# PDM-S04-V00-Microcontroller.net
KiCad netlist of a schematic drawn in Altium Designer
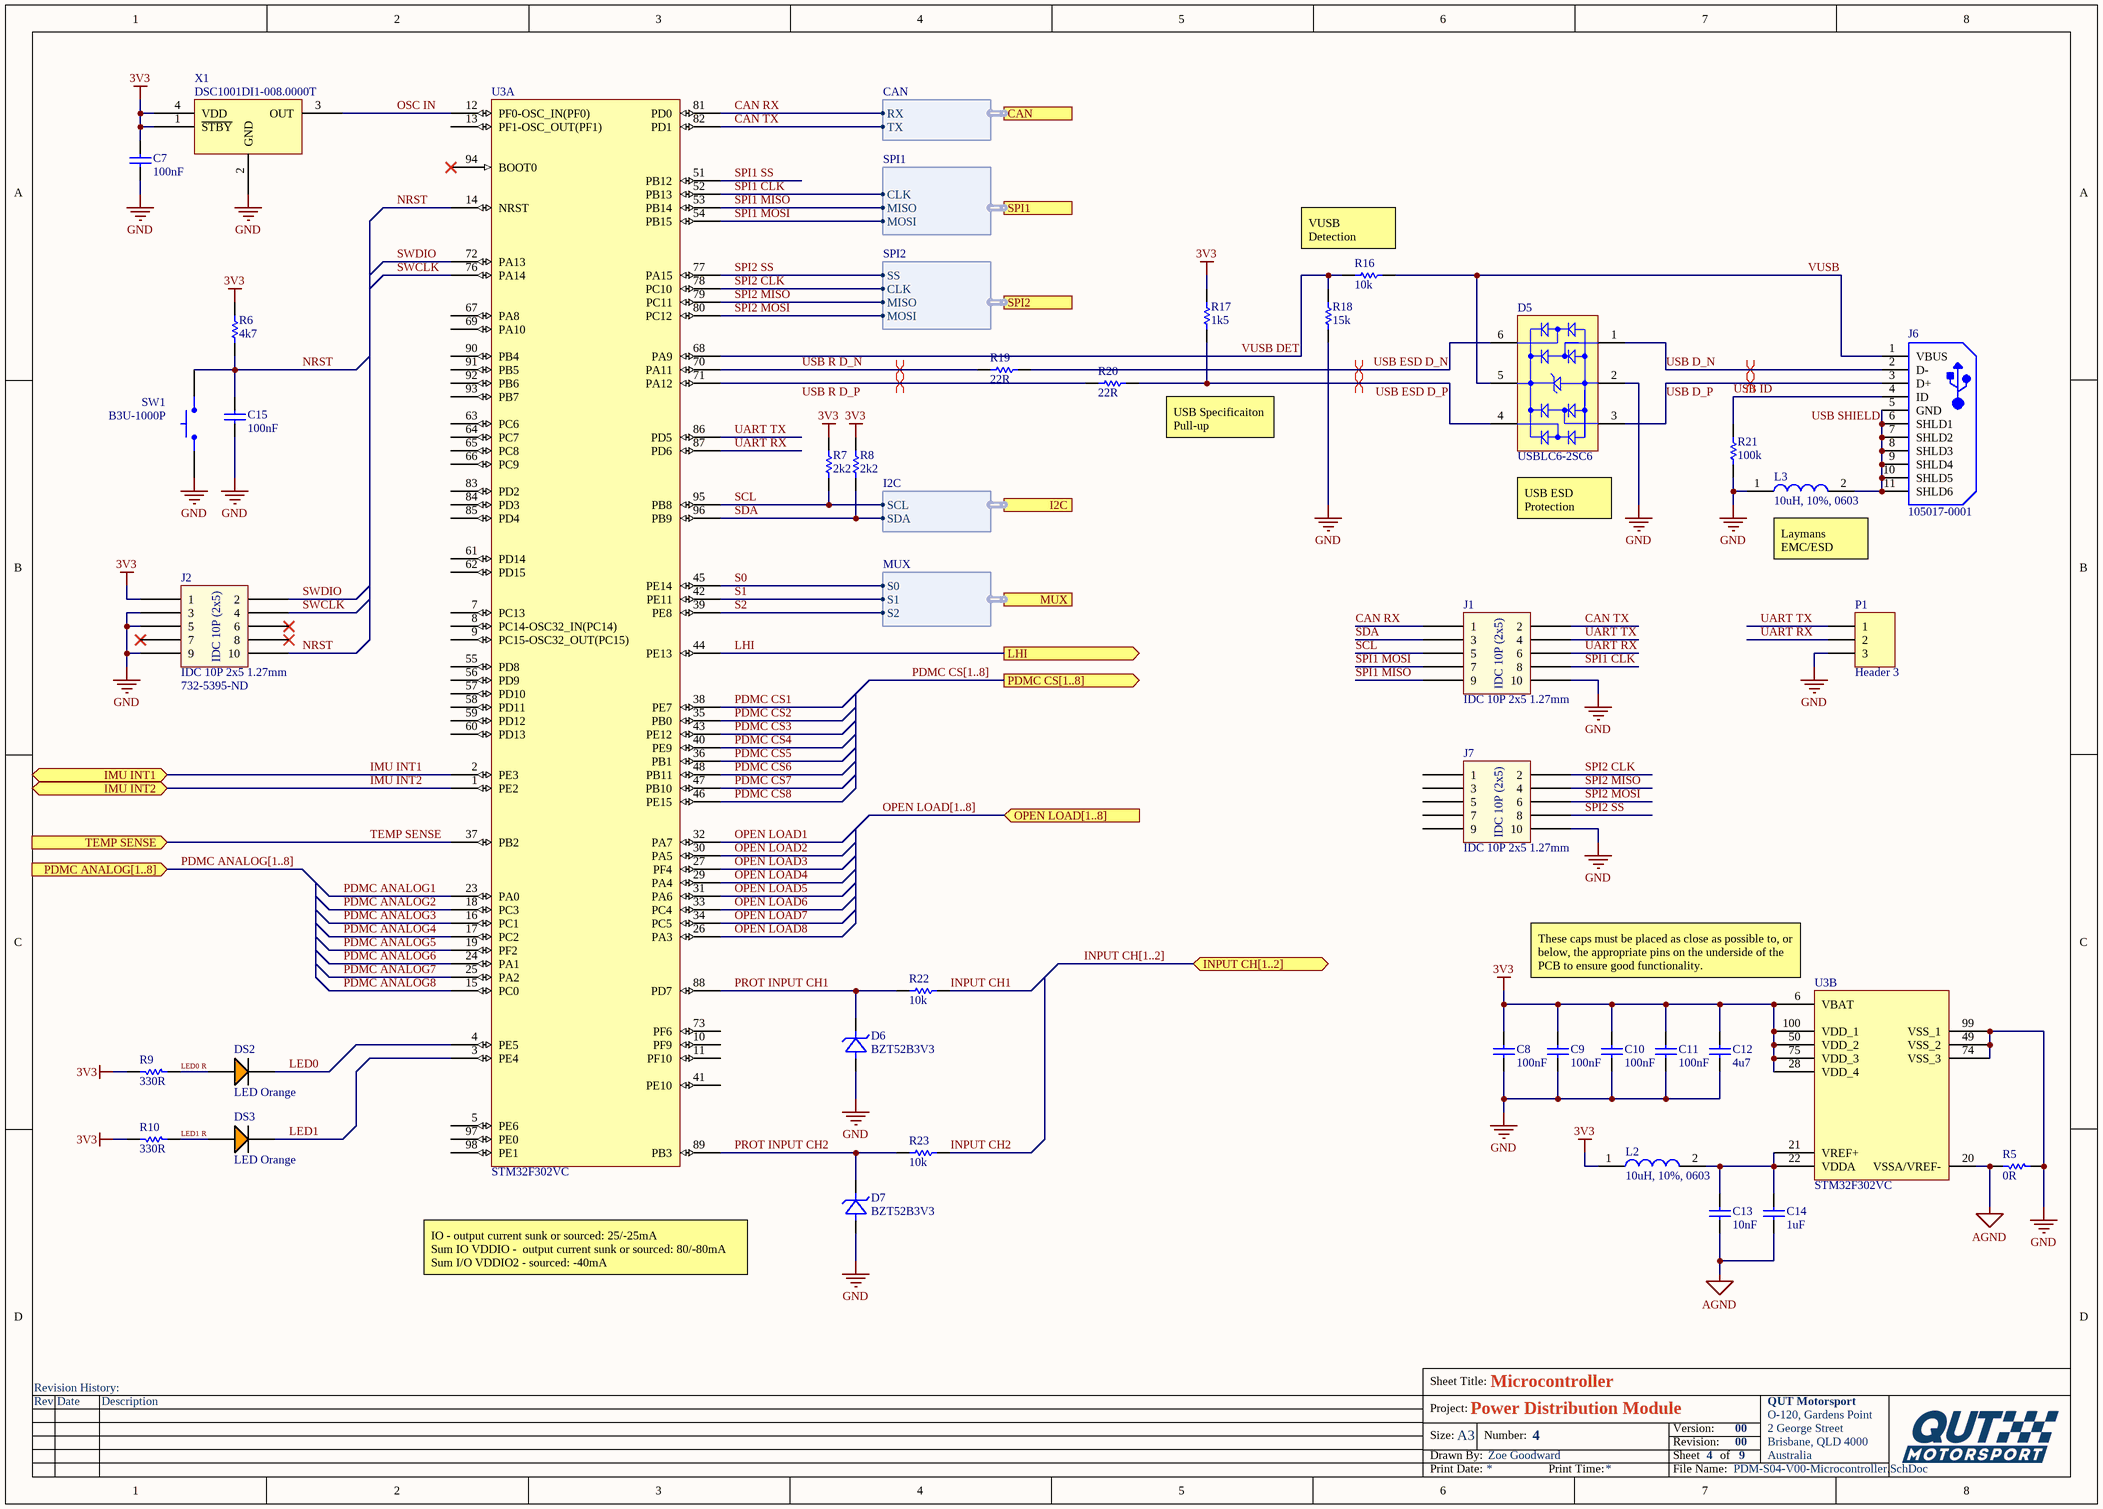
[diagram p0: PDM-S04-V00-Microcontroller.SchDoc]

(export (version "E")
  (design (tool "Eeschema 10.0.6"))
  (components
    (comp (ref "C7")
      (value "100nF")
      (footprint "Cap_Ceramic_0603")
      (description "Capacitor, Ceramic, SMD, 100nF, 50V, 5%, X7R, 0603")
      (libsource (lib "StandardCapacitors") (part "100nF 50V 5% X7R 0603"))
    )
    (comp (ref "C8")
      (value "100nF")
      (footprint "Cap_Ceramic_0603")
      (description "Capacitor, Ceramic, SMD, 100nF, 50V, 5%, X7R, 0603")
      (libsource (lib "StandardCapacitors") (part "100nF 50V 5% X7R 0603"))
    )
    (comp (ref "C9")
      (value "100nF")
      (footprint "Cap_Ceramic_0603")
      (description "Capacitor, Ceramic, SMD, 100nF, 50V, 5%, X7R, 0603")
      (libsource (lib "StandardCapacitors") (part "100nF 50V 5% X7R 0603"))
    )
    (comp (ref "C10")
      (value "100nF")
      (footprint "Cap_Ceramic_0603")
      (description "Capacitor, Ceramic, SMD, 100nF, 50V, 5%, X7R, 0603")
      (libsource (lib "StandardCapacitors") (part "100nF 50V 5% X7R 0603"))
    )
    (comp (ref "C11")
      (value "100nF")
      (footprint "Cap_Ceramic_0603")
      (description "Capacitor, Ceramic, SMD, 100nF, 50V, 5%, X7R, 0603")
      (libsource (lib "StandardCapacitors") (part "100nF 50V 5% X7R 0603"))
    )
    (comp (ref "C12")
      (value "4u7")
      (footprint "Cap_Ceramic_0603")
      (description "Capacitor, Ceramic, SMD, 4u7, 50V, 5%, X7R, 0603")
      (libsource (lib "StandardCapacitors") (part "4u7 50V 5% X7R 0603"))
    )
    (comp (ref "C13")
      (value "10nF")
      (footprint "Cap_Ceramic_0603")
      (description "Capacitor, Ceramic, SMD, 10nF, 50V, 5%, X7R, 0603")
      (libsource (lib "StandardCapacitors") (part "10nF 50V 5% X7R 0603"))
    )
    (comp (ref "C14")
      (value "1uF")
      (footprint "Cap_Ceramic_0603")
      (description "Capacitor, Ceramic, SMD, 1uF, 25V, 5%, X7R, 0603")
      (libsource (lib "StandardCapacitors") (part "1uF 25V 5% X7R 0603"))
    )
    (comp (ref "C15")
      (value "100nF")
      (footprint "Cap_Ceramic_0603")
      (description "Capacitor, Ceramic, SMD, 100nF, 50V, 5%, X7R, 0603")
      (libsource (lib "StandardCapacitors") (part "100nF 50V 5% X7R 0603"))
    )
    (comp (ref "D5")
      (value "USBLC6-2SC6")
      (footprint "STM-SOT23-6L_V")
      (description "Very low capacitance ESD protection, 3.5 pF, -40 to 125 degC, 6-Pin SOT23, RoHS, Tape and Reel")
      (fields (field (name "MANUFACTURER") "STMicroelectronics"))
      (libsource (lib "Altium Content Vault") (part "STM-USB_DVI_HDMIULC6-4SC6X-SOT23-6L"))
    )
    (comp (ref "D6")
      (value "BZT52B3V3")
      (footprint "SOD123")
      (description "Diode, SMD, Zener, 3.3V, 2%, 410mW, SOD-123")
      (libsource (lib "QUTMS_DiodeLibrary") (part "BZT52B3V3"))
    )
    (comp (ref "D7")
      (value "BZT52B3V3")
      (footprint "SOD123")
      (description "Diode, SMD, Zener, 3.3V, 2%, 410mW, SOD-123")
      (libsource (lib "QUTMS_DiodeLibrary") (part "BZT52B3V3"))
    )
    (comp (ref "DS2")
      (value "LED Orange")
      (footprint "LED ORANGE 0603")
      (libsource (lib "QUTMS_LEDLibrary") (part "LED ORANGE 0603"))
    )
    (comp (ref "DS3")
      (value "LED Orange")
      (footprint "LED ORANGE 0603")
      (libsource (lib "QUTMS_LEDLibrary") (part "LED ORANGE 0603"))
    )
    (comp (ref "J1")
      (value "IDC 10P 2x5 1.27mm")
      (footprint "IDC 1.27MM 10P")
      (libsource (lib "IDCConnectors") (part "IDC 10P 2x5 1.27mm"))
    )
    (comp (ref "J2")
      (value "IDC 10P 2x5 1.27mm")
      (footprint "IDC 1.27MM 10P")
      (libsource (lib "IDCConnectors") (part "IDC 10P 2x5 1.27mm"))
    )
    (comp (ref "J6")
      (value "105017-0001")
      (footprint "USB-MICRO-B_V")
      (fields (field (name "MANUFACTURER") "Molex"))
      (libsource (lib "Altium Content Vault") (part "USB-5-6SHLD"))
    )
    (comp (ref "J7")
      (value "IDC 10P 2x5 1.27mm")
      (footprint "IDC 1.27MM 10P")
      (libsource (lib "IDCConnectors") (part "IDC 10P 2x5 1.27mm"))
    )
    (comp (ref "L2")
      (value "10uH, 10%, 0603")
      (footprint "Inductor_0603")
      (libsource (lib "QUTMS_InductorLibrary") (part "10uH, 10%, 0603"))
    )
    (comp (ref "L3")
      (value "10uH, 10%, 0603")
      (footprint "Inductor_0603")
      (libsource (lib "QUTMS_InductorLibrary") (part "10uH, 10%, 0603"))
    )
    (comp (ref "P1")
      (value "Header 3")
      (footprint "HDR1X3")
      (description "Header, 3-Pin")
      (fields (field (name "PUBLISHER") "Altium Limited"))
      (libsource (lib "Miscellaneous Connectors") (part "Header 3"))
    )
    (comp (ref "R5")
      (value "0R")
      (footprint "Res_ThinFilm_0603")
      (description "Resistor, SMD, 0R, 0.1W, 5%, 0603")
      (libsource (lib "StandardResistors") (part "0R 5% 0603"))
    )
    (comp (ref "R6")
      (value "4k7")
      (footprint "Res_ThinFilm_0603")
      (description "Resistor, SMD, 4k7, 0.1W, 5%, 0603")
      (libsource (lib "StandardResistors") (part "4k7 5% 0603"))
    )
    (comp (ref "R7")
      (value "2k2")
      (footprint "Res_ThinFilm_0603")
      (description "Resistor, SMD, 2k2, 0.1W, 5%, 0603")
      (libsource (lib "StandardResistors") (part "2k2 5% 0603"))
    )
    (comp (ref "R8")
      (value "2k2")
      (footprint "Res_ThinFilm_0603")
      (description "Resistor, SMD, 2k2, 0.1W, 5%, 0603")
      (libsource (lib "StandardResistors") (part "2k2 5% 0603"))
    )
    (comp (ref "R9")
      (value "330R")
      (footprint "Res_ThinFilm_0603")
      (description "Resistor, SMD, 330R, 0.1W, 5%, 0603")
      (libsource (lib "StandardResistors") (part "330R 5% 0603"))
    )
    (comp (ref "R10")
      (value "330R")
      (footprint "Res_ThinFilm_0603")
      (description "Resistor, SMD, 330R, 0.1W, 5%, 0603")
      (libsource (lib "StandardResistors") (part "330R 5% 0603"))
    )
    (comp (ref "R16")
      (value "10k")
      (footprint "Res_ThinFilm_0603")
      (description "Resistor, SMD, 10k, 0.1W, 1%, 0603")
      (libsource (lib "StandardResistors") (part "10k 1% 0603"))
    )
    (comp (ref "R17")
      (value "1k5")
      (footprint "Res_ThinFilm_0603")
      (description "Resistor, SMD, 1k5, 0.1W, 5%, 0603")
      (libsource (lib "StandardResistors") (part "1k5 5% 0603"))
    )
    (comp (ref "R18")
      (value "15k")
      (footprint "Res_ThinFilm_0603")
      (description "Resistor, SMD, 15k, 0.1W, 5%, 0603")
      (libsource (lib "StandardResistors") (part "15k 5% 0603"))
    )
    (comp (ref "R19")
      (value "22R")
      (footprint "Res_ThinFilm_0603")
      (description "Resistor, SMD, 22R, 0.1W, 5%, 0603")
      (libsource (lib "StandardResistors") (part "22R 5% 0603"))
    )
    (comp (ref "R20")
      (value "22R")
      (footprint "Res_ThinFilm_0603")
      (description "Resistor, SMD, 22R, 0.1W, 5%, 0603")
      (libsource (lib "StandardResistors") (part "22R 5% 0603"))
    )
    (comp (ref "R21")
      (value "100k")
      (footprint "Res_ThinFilm_0603")
      (description "Resistor, SMD, 100k, 0.1W, 5%, 0603")
      (libsource (lib "StandardResistors") (part "100k 5%, 0603"))
    )
    (comp (ref "R22")
      (value "10k")
      (footprint "Res_ThinFilm_0603")
      (description "Resistor, SMD, 10k, 0.1W, 5%, 0603")
      (libsource (lib "StandardResistors") (part "10k 5% 0603"))
    )
    (comp (ref "R23")
      (value "10k")
      (footprint "Res_ThinFilm_0603")
      (description "Resistor, SMD, 10k, 0.1W, 5%, 0603")
      (libsource (lib "StandardResistors") (part "10k 5% 0603"))
    )
    (comp (ref "SW1")
      (value "B3U-1000P")
      (footprint "BTN B3U-1000P")
      (description "Omron B3U-1000P Ultra Miniture Switch")
      (libsource (lib "QUTMS_SwitchLibrary") (part "BTN B3U-1000P"))
    )
    (comp (ref "U3")
      (value "STM32F302VC")
      (footprint "STM-LQFP100")
      (description "ARM Cortex-M4 32-bit MCU, 256 KB Flash, 32 KB Internal RAM, 87 I/Os, 100-pin LQFP, -40 to 85 degC")
      (fields (field (name "PARTNUMBER") "STM32F302VCT6"))
      (libsource (lib "QUTMS_STM32Library") (part "STM32F302VC"))
    )
    (comp (ref "X1")
      (value "DSC1001DI1-008.0000T")
      (footprint "DSC1001DI1-008.0000TCT-ND")
      (description "8MHz XO (Standard) CMOS Oscillator 1.8 ~ 3.3V Standby (Power Down) 4-SMD, No Lead")
      (libsource (lib "QUTMS_CrystalLibrary") (part "DSC1001DI1-008.0000T"))
    )
  )
  (nets
    (net (code "6") (name "/CAN RX") (class "Default")
      (node (ref "J1") (pin "1") (pinfunction "1_1") (pintype "passive"))
      (node (ref "U3") (pin "81") (pinfunction "PD0_81") (pintype "bidirectional"))
    )
    (net (code "7") (name "/CAN TX") (class "Default")
      (node (ref "J1") (pin "2") (pinfunction "2_2") (pintype "passive"))
      (node (ref "U3") (pin "82") (pinfunction "PD1_82") (pintype "bidirectional"))
    )
    (net (code "8") (name "/IMU INT1") (class "Default")
      (node (ref "U3") (pin "2") (pinfunction "PE3_2") (pintype "bidirectional"))
    )
    (net (code "9") (name "/IMU INT2") (class "Default")
      (node (ref "U3") (pin "1") (pinfunction "PE2_1") (pintype "bidirectional"))
    )
    (net (code "10") (name "/INPUT CH1") (class "Default")
      (node (ref "R22") (pin "2") (pinfunction "2_2") (pintype "passive"))
    )
    (net (code "11") (name "/INPUT CH2") (class "Default")
      (node (ref "R23") (pin "2") (pinfunction "2_2") (pintype "passive"))
    )
    (net (code "12") (name "/LED0") (class "Default")
      (node (ref "DS2") (pin "2") (pinfunction "C_2") (pintype "passive"))
      (node (ref "U3") (pin "4") (pinfunction "PE5_4") (pintype "bidirectional"))
    )
    (net (code "13") (name "/LED0 R") (class "Default")
      (node (ref "DS2") (pin "1") (pinfunction "A_1") (pintype "passive"))
      (node (ref "R9") (pin "1") (pinfunction "1_1") (pintype "passive"))
    )
    (net (code "14") (name "/LED1") (class "Default")
      (node (ref "DS3") (pin "2") (pinfunction "C_2") (pintype "passive"))
      (node (ref "U3") (pin "3") (pinfunction "PE4_3") (pintype "bidirectional"))
    )
    (net (code "15") (name "/LED1 R") (class "Default")
      (node (ref "DS3") (pin "1") (pinfunction "A_1") (pintype "passive"))
      (node (ref "R10") (pin "1") (pinfunction "1_1") (pintype "passive"))
    )
    (net (code "16") (name "/LHI") (class "Default")
      (node (ref "U3") (pin "44") (pinfunction "PE13_44") (pintype "bidirectional"))
    )
    (net (code "17") (name "/NRST") (class "Default")
      (node (ref "C15") (pin "2") (pinfunction "2_2") (pintype "passive"))
      (node (ref "J2") (pin "10") (pinfunction "10_10") (pintype "passive"))
      (node (ref "R6") (pin "1") (pinfunction "1_1") (pintype "passive"))
      (node (ref "SW1") (pin "2") (pinfunction "2_2") (pintype "passive"))
      (node (ref "U3") (pin "14") (pinfunction "NRST_14") (pintype "bidirectional"))
    )
    (net (code "18") (name "/OPEN LOAD1") (class "Default")
      (node (ref "U3") (pin "32") (pinfunction "PA7_32") (pintype "bidirectional"))
    )
    (net (code "19") (name "/OPEN LOAD2") (class "Default")
      (node (ref "U3") (pin "30") (pinfunction "PA5_30") (pintype "bidirectional"))
    )
    (net (code "20") (name "/OPEN LOAD3") (class "Default")
      (node (ref "U3") (pin "27") (pinfunction "PF4_27") (pintype "bidirectional"))
    )
    (net (code "21") (name "/OPEN LOAD4") (class "Default")
      (node (ref "U3") (pin "29") (pinfunction "PA4_29") (pintype "bidirectional"))
    )
    (net (code "22") (name "/OPEN LOAD5") (class "Default")
      (node (ref "U3") (pin "31") (pinfunction "PA6_31") (pintype "bidirectional"))
    )
    (net (code "23") (name "/OPEN LOAD6") (class "Default")
      (node (ref "U3") (pin "33") (pinfunction "PC4_33") (pintype "bidirectional"))
    )
    (net (code "24") (name "/OPEN LOAD7") (class "Default")
      (node (ref "U3") (pin "34") (pinfunction "PC5_34") (pintype "bidirectional"))
    )
    (net (code "25") (name "/OPEN LOAD8") (class "Default")
      (node (ref "U3") (pin "26") (pinfunction "PA3_26") (pintype "bidirectional"))
    )
    (net (code "26") (name "/OSC IN") (class "Default")
      (node (ref "U3") (pin "12") (pinfunction "PF0-OSC_IN(PF0)_12") (pintype "bidirectional"))
      (node (ref "X1") (pin "3") (pinfunction "OUT_3") (pintype "passive"))
    )
    (net (code "27") (name "/PDMC ANALOG1") (class "Default")
      (node (ref "U3") (pin "23") (pinfunction "PA0_23") (pintype "bidirectional"))
    )
    (net (code "28") (name "/PDMC ANALOG2") (class "Default")
      (node (ref "U3") (pin "18") (pinfunction "PC3_18") (pintype "bidirectional"))
    )
    (net (code "29") (name "/PDMC ANALOG3") (class "Default")
      (node (ref "U3") (pin "16") (pinfunction "PC1_16") (pintype "bidirectional"))
    )
    (net (code "30") (name "/PDMC ANALOG4") (class "Default")
      (node (ref "U3") (pin "17") (pinfunction "PC2_17") (pintype "bidirectional"))
    )
    (net (code "31") (name "/PDMC ANALOG5") (class "Default")
      (node (ref "U3") (pin "19") (pinfunction "PF2_19") (pintype "bidirectional"))
    )
    (net (code "32") (name "/PDMC ANALOG6") (class "Default")
      (node (ref "U3") (pin "24") (pinfunction "PA1_24") (pintype "bidirectional"))
    )
    (net (code "33") (name "/PDMC ANALOG7") (class "Default")
      (node (ref "U3") (pin "25") (pinfunction "PA2_25") (pintype "bidirectional"))
    )
    (net (code "34") (name "/PDMC ANALOG8") (class "Default")
      (node (ref "U3") (pin "15") (pinfunction "PC0_15") (pintype "bidirectional"))
    )
    (net (code "35") (name "/PDMC CS1") (class "Default")
      (node (ref "U3") (pin "38") (pinfunction "PE7_38") (pintype "bidirectional"))
    )
    (net (code "36") (name "/PDMC CS2") (class "Default")
      (node (ref "U3") (pin "35") (pinfunction "PB0_35") (pintype "bidirectional"))
    )
    (net (code "37") (name "/PDMC CS3") (class "Default")
      (node (ref "U3") (pin "43") (pinfunction "PE12_43") (pintype "bidirectional"))
    )
    (net (code "38") (name "/PDMC CS4") (class "Default")
      (node (ref "U3") (pin "40") (pinfunction "PE9_40") (pintype "bidirectional"))
    )
    (net (code "39") (name "/PDMC CS5") (class "Default")
      (node (ref "U3") (pin "36") (pinfunction "PB1_36") (pintype "bidirectional"))
    )
    (net (code "40") (name "/PDMC CS6") (class "Default")
      (node (ref "U3") (pin "48") (pinfunction "PB11_48") (pintype "bidirectional"))
    )
    (net (code "41") (name "/PDMC CS7") (class "Default")
      (node (ref "U3") (pin "47") (pinfunction "PB10_47") (pintype "bidirectional"))
    )
    (net (code "42") (name "/PDMC CS8") (class "Default")
      (node (ref "U3") (pin "46") (pinfunction "PE15_46") (pintype "bidirectional"))
    )
    (net (code "43") (name "/PROT INPUT CH1") (class "Default")
      (node (ref "D6") (pin "K") (pinfunction "Cathode_K") (pintype "passive"))
      (node (ref "R22") (pin "1") (pinfunction "1_1") (pintype "passive"))
      (node (ref "U3") (pin "88") (pinfunction "PD7_88") (pintype "bidirectional"))
    )
    (net (code "44") (name "/PROT INPUT CH2") (class "Default")
      (node (ref "D7") (pin "K") (pinfunction "Cathode_K") (pintype "passive"))
      (node (ref "R23") (pin "1") (pinfunction "1_1") (pintype "passive"))
      (node (ref "U3") (pin "89") (pinfunction "PB3_89") (pintype "bidirectional"))
    )
    (net (code "45") (name "/S0") (class "Default")
      (node (ref "U3") (pin "45") (pinfunction "PE14_45") (pintype "bidirectional"))
    )
    (net (code "46") (name "/S1") (class "Default")
      (node (ref "U3") (pin "42") (pinfunction "PE11_42") (pintype "bidirectional"))
    )
    (net (code "47") (name "/S2") (class "Default")
      (node (ref "U3") (pin "39") (pinfunction "PE8_39") (pintype "bidirectional"))
    )
    (net (code "48") (name "/SCL") (class "Default")
      (node (ref "J1") (pin "5") (pinfunction "5_5") (pintype "passive"))
      (node (ref "R7") (pin "1") (pinfunction "1_1") (pintype "passive"))
      (node (ref "U3") (pin "95") (pinfunction "PB8_95") (pintype "bidirectional"))
    )
    (net (code "49") (name "/SDA") (class "Default")
      (node (ref "J1") (pin "3") (pinfunction "3_3") (pintype "passive"))
      (node (ref "R8") (pin "1") (pinfunction "1_1") (pintype "passive"))
      (node (ref "U3") (pin "96") (pinfunction "PB9_96") (pintype "bidirectional"))
    )
    (net (code "50") (name "/SPI1 CLK") (class "Default")
      (node (ref "J1") (pin "8") (pinfunction "8_8") (pintype "passive"))
      (node (ref "U3") (pin "52") (pinfunction "PB13_52") (pintype "bidirectional"))
    )
    (net (code "51") (name "/SPI1 MISO") (class "Default")
      (node (ref "J1") (pin "9") (pinfunction "9_9") (pintype "passive"))
      (node (ref "U3") (pin "53") (pinfunction "PB14_53") (pintype "bidirectional"))
    )
    (net (code "52") (name "/SPI1 MOSI") (class "Default")
      (node (ref "J1") (pin "7") (pinfunction "7_7") (pintype "passive"))
      (node (ref "U3") (pin "54") (pinfunction "PB15_54") (pintype "bidirectional"))
    )
    (net (code "53") (name "/SPI1 SS") (class "Default")
      (node (ref "U3") (pin "51") (pinfunction "PB12_51") (pintype "bidirectional"))
    )
    (net (code "54") (name "/SPI2 CLK") (class "Default")
      (node (ref "J7") (pin "2") (pinfunction "2_2") (pintype "passive"))
      (node (ref "U3") (pin "78") (pinfunction "PC10_78") (pintype "bidirectional"))
    )
    (net (code "55") (name "/SPI2 MISO") (class "Default")
      (node (ref "J7") (pin "4") (pinfunction "4_4") (pintype "passive"))
      (node (ref "U3") (pin "79") (pinfunction "PC11_79") (pintype "bidirectional"))
    )
    (net (code "56") (name "/SPI2 MOSI") (class "Default")
      (node (ref "J7") (pin "6") (pinfunction "6_6") (pintype "passive"))
      (node (ref "U3") (pin "80") (pinfunction "PC12_80") (pintype "bidirectional"))
    )
    (net (code "57") (name "/SPI2 SS") (class "Default")
      (node (ref "J7") (pin "8") (pinfunction "8_8") (pintype "passive"))
      (node (ref "U3") (pin "77") (pinfunction "PA15_77") (pintype "bidirectional"))
    )
    (net (code "58") (name "/SWCLK") (class "Default")
      (node (ref "J2") (pin "4") (pinfunction "4_4") (pintype "passive"))
      (node (ref "U3") (pin "76") (pinfunction "PA14_76") (pintype "bidirectional"))
    )
    (net (code "59") (name "/SWDIO") (class "Default")
      (node (ref "J2") (pin "2") (pinfunction "2_2") (pintype "passive"))
      (node (ref "U3") (pin "72") (pinfunction "PA13_72") (pintype "bidirectional"))
    )
    (net (code "60") (name "/TEMP SENSE") (class "Default")
      (node (ref "U3") (pin "37") (pinfunction "PB2_37") (pintype "bidirectional"))
    )
    (net (code "61") (name "/UART RX") (class "Default")
      (node (ref "J1") (pin "6") (pinfunction "6_6") (pintype "passive"))
      (node (ref "P1") (pin "2") (pinfunction "2_2") (pintype "passive"))
      (node (ref "U3") (pin "87") (pinfunction "PD6_87") (pintype "bidirectional"))
    )
    (net (code "62") (name "/UART TX") (class "Default")
      (node (ref "J1") (pin "4") (pinfunction "4_4") (pintype "passive"))
      (node (ref "P1") (pin "1") (pinfunction "1_1") (pintype "passive"))
      (node (ref "U3") (pin "86") (pinfunction "PD5_86") (pintype "bidirectional"))
    )
    (net (code "63") (name "/USB D_N") (class "Default")
      (node (ref "D5") (pin "1") (pinfunction "I/O_1_1") (pintype "passive"))
      (node (ref "J6") (pin "2") (pinfunction "D-_2") (pintype "passive"))
    )
    (net (code "64") (name "/USB D_P") (class "Default")
      (node (ref "D5") (pin "3") (pinfunction "I/O_2_3") (pintype "passive"))
      (node (ref "J6") (pin "3") (pinfunction "D+_3") (pintype "passive"))
    )
    (net (code "65") (name "/USB ESD D_N") (class "Default")
      (node (ref "D5") (pin "6") (pinfunction "I/O_4_6") (pintype "passive"))
      (node (ref "R19") (pin "2") (pinfunction "2_2") (pintype "passive"))
    )
    (net (code "66") (name "/USB ESD D_P") (class "Default")
      (node (ref "D5") (pin "4") (pinfunction "I/O_3_4") (pintype "passive"))
      (node (ref "R17") (pin "1") (pinfunction "1_1") (pintype "passive"))
      (node (ref "R20") (pin "2") (pinfunction "2_2") (pintype "passive"))
    )
    (net (code "67") (name "/USB ID") (class "Default")
      (node (ref "J6") (pin "4") (pinfunction "ID_4") (pintype "passive"))
      (node (ref "R21") (pin "2") (pinfunction "2_2") (pintype "passive"))
    )
    (net (code "68") (name "/USB R D_N") (class "Default")
      (node (ref "R19") (pin "1") (pinfunction "1_1") (pintype "passive"))
      (node (ref "U3") (pin "70") (pinfunction "PA11_70") (pintype "bidirectional"))
    )
    (net (code "69") (name "/USB R D_P") (class "Default")
      (node (ref "R20") (pin "1") (pinfunction "1_1") (pintype "passive"))
      (node (ref "U3") (pin "71") (pinfunction "PA12_71") (pintype "bidirectional"))
    )
    (net (code "70") (name "/USB SHIELD") (class "Default")
      (node (ref "J6") (pin "10") (pinfunction "SHLD5_10") (pintype "passive"))
      (node (ref "J6") (pin "11") (pinfunction "SHLD6_11") (pintype "passive"))
      (node (ref "J6") (pin "5") (pinfunction "GND_5") (pintype "passive"))
      (node (ref "J6") (pin "6") (pinfunction "SHLD1_6") (pintype "passive"))
      (node (ref "J6") (pin "7") (pinfunction "SHLD2_7") (pintype "passive"))
      (node (ref "J6") (pin "8") (pinfunction "SHLD3_8") (pintype "passive"))
      (node (ref "J6") (pin "9") (pinfunction "SHLD4_9") (pintype "passive"))
      (node (ref "L3") (pin "2") (pinfunction "2_2") (pintype "passive"))
    )
    (net (code "71") (name "/VUSB") (class "Default")
      (node (ref "D5") (pin "5") (pinfunction "VBUS_5") (pintype "passive"))
      (node (ref "J6") (pin "1") (pinfunction "VBUS_1") (pintype "passive"))
      (node (ref "R16") (pin "2") (pinfunction "2_2") (pintype "passive"))
    )
    (net (code "72") (name "/VUSB DET") (class "Default")
      (node (ref "R16") (pin "1") (pinfunction "1_1") (pintype "passive"))
      (node (ref "R18") (pin "2") (pinfunction "2_2") (pintype "passive"))
      (node (ref "U3") (pin "68") (pinfunction "PA9_68") (pintype "bidirectional"))
    )
    (net (code "82") (name "3V3") (class "Default")
      (node (ref "C10") (pin "2") (pinfunction "2_2") (pintype "passive"))
      (node (ref "C11") (pin "2") (pinfunction "2_2") (pintype "passive"))
      (node (ref "C12") (pin "2") (pinfunction "2_2") (pintype "passive"))
      (node (ref "C7") (pin "2") (pinfunction "2_2") (pintype "passive"))
      (node (ref "C8") (pin "2") (pinfunction "2_2") (pintype "passive"))
      (node (ref "C9") (pin "2") (pinfunction "2_2") (pintype "passive"))
      (node (ref "J2") (pin "1") (pinfunction "1_1") (pintype "passive"))
      (node (ref "L2") (pin "1") (pinfunction "1_1") (pintype "passive"))
      (node (ref "R10") (pin "2") (pinfunction "2_2") (pintype "passive"))
      (node (ref "R17") (pin "2") (pinfunction "2_2") (pintype "passive"))
      (node (ref "R6") (pin "2") (pinfunction "2_2") (pintype "passive"))
      (node (ref "R7") (pin "2") (pinfunction "2_2") (pintype "passive"))
      (node (ref "R8") (pin "2") (pinfunction "2_2") (pintype "passive"))
      (node (ref "R9") (pin "2") (pinfunction "2_2") (pintype "passive"))
      (node (ref "U3") (pin "100") (pinfunction "VDD_1_100") (pintype "power_in"))
      (node (ref "U3") (pin "28") (pinfunction "VDD_4_28") (pintype "power_in"))
      (node (ref "U3") (pin "50") (pinfunction "VDD_2_50") (pintype "power_in"))
      (node (ref "U3") (pin "6") (pinfunction "VBAT_6") (pintype "power_in"))
      (node (ref "U3") (pin "75") (pinfunction "VDD_3_75") (pintype "power_in"))
      (node (ref "X1") (pin "1") (pinfunction "~{STBY}_1") (pintype "passive"))
      (node (ref "X1") (pin "4") (pinfunction "VDD_4") (pintype "passive"))
    )
    (net (code "83") (name "AGND") (class "Default")
      (node (ref "C13") (pin "1") (pinfunction "1_1") (pintype "passive"))
      (node (ref "C14") (pin "1") (pinfunction "1_1") (pintype "passive"))
      (node (ref "R5") (pin "2") (pinfunction "2_2") (pintype "passive"))
      (node (ref "U3") (pin "20") (pinfunction "VSSA/VREF-_20") (pintype "power_in"))
    )
    (net (code "84") (name "GND") (class "Default")
      (node (ref "C10") (pin "1") (pinfunction "1_1") (pintype "passive"))
      (node (ref "C11") (pin "1") (pinfunction "1_1") (pintype "passive"))
      (node (ref "C12") (pin "1") (pinfunction "1_1") (pintype "passive"))
      (node (ref "C15") (pin "1") (pinfunction "1_1") (pintype "passive"))
      (node (ref "C7") (pin "1") (pinfunction "1_1") (pintype "passive"))
      (node (ref "C8") (pin "1") (pinfunction "1_1") (pintype "passive"))
      (node (ref "C9") (pin "1") (pinfunction "1_1") (pintype "passive"))
      (node (ref "D5") (pin "2") (pinfunction "GND_2") (pintype "passive"))
      (node (ref "D6") (pin "A") (pinfunction "Anode_A") (pintype "passive"))
      (node (ref "D7") (pin "A") (pinfunction "Anode_A") (pintype "passive"))
      (node (ref "J1") (pin "10") (pinfunction "10_10") (pintype "passive"))
      (node (ref "J2") (pin "3") (pinfunction "3_3") (pintype "passive"))
      (node (ref "J2") (pin "5") (pinfunction "5_5") (pintype "passive"))
      (node (ref "J2") (pin "9") (pinfunction "9_9") (pintype "passive"))
      (node (ref "J7") (pin "10") (pinfunction "10_10") (pintype "passive"))
      (node (ref "L3") (pin "1") (pinfunction "1_1") (pintype "passive"))
      (node (ref "P1") (pin "3") (pinfunction "3_3") (pintype "passive"))
      (node (ref "R18") (pin "1") (pinfunction "1_1") (pintype "passive"))
      (node (ref "R21") (pin "1") (pinfunction "1_1") (pintype "passive"))
      (node (ref "R5") (pin "1") (pinfunction "1_1") (pintype "passive"))
      (node (ref "SW1") (pin "1") (pinfunction "1_1") (pintype "passive"))
      (node (ref "U3") (pin "49") (pinfunction "VSS_2_49") (pintype "power_in"))
      (node (ref "U3") (pin "74") (pinfunction "VSS_3_74") (pintype "power_in"))
      (node (ref "U3") (pin "99") (pinfunction "VSS_1_99") (pintype "power_in"))
      (node (ref "X1") (pin "2") (pinfunction "GND_2") (pintype "passive"))
    )
    (net (code "85") (name "Net-(U3B-VDDA)") (class "Default")
      (node (ref "C13") (pin "2") (pinfunction "2_2") (pintype "passive"))
      (node (ref "C14") (pin "2") (pinfunction "2_2") (pintype "passive"))
      (node (ref "L2") (pin "2") (pinfunction "2_2") (pintype "passive"))
      (node (ref "U3") (pin "21") (pinfunction "VREF+_21") (pintype "power_in"))
      (node (ref "U3") (pin "22") (pinfunction "VDDA_22") (pintype "power_in"))
    )
    (net (code "86") (name "unconnected-(J2-Pad6)") (class "Default")
      (node (ref "J2") (pin "6") (pinfunction "6_6") (pintype "passive+no_connect"))
    )
    (net (code "87") (name "unconnected-(J2-Pad7)") (class "Default")
      (node (ref "J2") (pin "7") (pinfunction "7_7") (pintype "passive+no_connect"))
    )
    (net (code "88") (name "unconnected-(J2-Pad8)") (class "Default")
      (node (ref "J2") (pin "8") (pinfunction "8_8") (pintype "passive+no_connect"))
    )
    (net (code "89") (name "unconnected-(J7-Pad1)") (class "Default")
      (node (ref "J7") (pin "1") (pinfunction "1_1") (pintype "passive"))
    )
    (net (code "90") (name "unconnected-(J7-Pad3)") (class "Default")
      (node (ref "J7") (pin "3") (pinfunction "3_3") (pintype "passive"))
    )
    (net (code "91") (name "unconnected-(J7-Pad5)") (class "Default")
      (node (ref "J7") (pin "5") (pinfunction "5_5") (pintype "passive"))
    )
    (net (code "92") (name "unconnected-(J7-Pad7)") (class "Default")
      (node (ref "J7") (pin "7") (pinfunction "7_7") (pintype "passive"))
    )
    (net (code "93") (name "unconnected-(J7-Pad9)") (class "Default")
      (node (ref "J7") (pin "9") (pinfunction "9_9") (pintype "passive"))
    )
    (net (code "94") (name "unconnected-(U3A-BOOT0-Pad94)") (class "Default")
      (node (ref "U3") (pin "94") (pinfunction "BOOT0_94") (pintype "input+no_connect"))
    )
    (net (code "95") (name "unconnected-(U3A-PA8-Pad67)") (class "Default")
      (node (ref "U3") (pin "67") (pinfunction "PA8_67") (pintype "bidirectional"))
    )
    (net (code "96") (name "unconnected-(U3A-PA10-Pad69)") (class "Default")
      (node (ref "U3") (pin "69") (pinfunction "PA10_69") (pintype "bidirectional"))
    )
    (net (code "97") (name "unconnected-(U3A-PB4-Pad90)") (class "Default")
      (node (ref "U3") (pin "90") (pinfunction "PB4_90") (pintype "bidirectional"))
    )
    (net (code "98") (name "unconnected-(U3A-PB5-Pad91)") (class "Default")
      (node (ref "U3") (pin "91") (pinfunction "PB5_91") (pintype "bidirectional"))
    )
    (net (code "99") (name "unconnected-(U3A-PB6-Pad92)") (class "Default")
      (node (ref "U3") (pin "92") (pinfunction "PB6_92") (pintype "bidirectional"))
    )
    (net (code "100") (name "unconnected-(U3A-PB7-Pad93)") (class "Default")
      (node (ref "U3") (pin "93") (pinfunction "PB7_93") (pintype "bidirectional"))
    )
    (net (code "101") (name "unconnected-(U3A-PC6-Pad63)") (class "Default")
      (node (ref "U3") (pin "63") (pinfunction "PC6_63") (pintype "bidirectional"))
    )
    (net (code "102") (name "unconnected-(U3A-PC7-Pad64)") (class "Default")
      (node (ref "U3") (pin "64") (pinfunction "PC7_64") (pintype "bidirectional"))
    )
    (net (code "103") (name "unconnected-(U3A-PC8-Pad65)") (class "Default")
      (node (ref "U3") (pin "65") (pinfunction "PC8_65") (pintype "bidirectional"))
    )
    (net (code "104") (name "unconnected-(U3A-PC9-Pad66)") (class "Default")
      (node (ref "U3") (pin "66") (pinfunction "PC9_66") (pintype "bidirectional"))
    )
    (net (code "105") (name "unconnected-(U3A-PC13-Pad7)") (class "Default")
      (node (ref "U3") (pin "7") (pinfunction "PC13_7") (pintype "bidirectional"))
    )
    (net (code "106") (name "unconnected-(U3A-PC14-OSC32_IN(PC14)-Pad8)") (class "Default")
      (node (ref "U3") (pin "8") (pinfunction "PC14-OSC32_IN(PC14)_8") (pintype "bidirectional"))
    )
    (net (code "107") (name "unconnected-(U3A-PC15-OSC32_OUT(PC15)-Pad9)") (class "Default")
      (node (ref "U3") (pin "9") (pinfunction "PC15-OSC32_OUT(PC15)_9") (pintype "bidirectional"))
    )
    (net (code "108") (name "unconnected-(U3A-PD2-Pad83)") (class "Default")
      (node (ref "U3") (pin "83") (pinfunction "PD2_83") (pintype "bidirectional"))
    )
    (net (code "109") (name "unconnected-(U3A-PD3-Pad84)") (class "Default")
      (node (ref "U3") (pin "84") (pinfunction "PD3_84") (pintype "bidirectional"))
    )
    (net (code "110") (name "unconnected-(U3A-PD4-Pad85)") (class "Default")
      (node (ref "U3") (pin "85") (pinfunction "PD4_85") (pintype "bidirectional"))
    )
    (net (code "111") (name "unconnected-(U3A-PD8-Pad55)") (class "Default")
      (node (ref "U3") (pin "55") (pinfunction "PD8_55") (pintype "bidirectional"))
    )
    (net (code "112") (name "unconnected-(U3A-PD9-Pad56)") (class "Default")
      (node (ref "U3") (pin "56") (pinfunction "PD9_56") (pintype "bidirectional"))
    )
    (net (code "113") (name "unconnected-(U3A-PD10-Pad57)") (class "Default")
      (node (ref "U3") (pin "57") (pinfunction "PD10_57") (pintype "bidirectional"))
    )
    (net (code "114") (name "unconnected-(U3A-PD11-Pad58)") (class "Default")
      (node (ref "U3") (pin "58") (pinfunction "PD11_58") (pintype "bidirectional"))
    )
    (net (code "115") (name "unconnected-(U3A-PD12-Pad59)") (class "Default")
      (node (ref "U3") (pin "59") (pinfunction "PD12_59") (pintype "bidirectional"))
    )
    (net (code "116") (name "unconnected-(U3A-PD13-Pad60)") (class "Default")
      (node (ref "U3") (pin "60") (pinfunction "PD13_60") (pintype "bidirectional"))
    )
    (net (code "117") (name "unconnected-(U3A-PD14-Pad61)") (class "Default")
      (node (ref "U3") (pin "61") (pinfunction "PD14_61") (pintype "bidirectional"))
    )
    (net (code "118") (name "unconnected-(U3A-PD15-Pad62)") (class "Default")
      (node (ref "U3") (pin "62") (pinfunction "PD15_62") (pintype "bidirectional"))
    )
    (net (code "119") (name "unconnected-(U3A-PE0-Pad97)") (class "Default")
      (node (ref "U3") (pin "97") (pinfunction "PE0_97") (pintype "bidirectional"))
    )
    (net (code "120") (name "unconnected-(U3A-PE1-Pad98)") (class "Default")
      (node (ref "U3") (pin "98") (pinfunction "PE1_98") (pintype "bidirectional"))
    )
    (net (code "121") (name "unconnected-(U3A-PE6-Pad5)") (class "Default")
      (node (ref "U3") (pin "5") (pinfunction "PE6_5") (pintype "bidirectional"))
    )
    (net (code "122") (name "unconnected-(U3A-PE10-Pad41)") (class "Default")
      (node (ref "U3") (pin "41") (pinfunction "PE10_41") (pintype "bidirectional"))
    )
    (net (code "123") (name "unconnected-(U3A-PF1-OSC_OUT(PF1)-Pad13)") (class "Default")
      (node (ref "U3") (pin "13") (pinfunction "PF1-OSC_OUT(PF1)_13") (pintype "bidirectional"))
    )
    (net (code "124") (name "unconnected-(U3A-PF6-Pad73)") (class "Default")
      (node (ref "U3") (pin "73") (pinfunction "PF6_73") (pintype "bidirectional"))
    )
    (net (code "125") (name "unconnected-(U3A-PF9-Pad10)") (class "Default")
      (node (ref "U3") (pin "10") (pinfunction "PF9_10") (pintype "bidirectional"))
    )
    (net (code "126") (name "unconnected-(U3A-PF10-Pad11)") (class "Default")
      (node (ref "U3") (pin "11") (pinfunction "PF10_11") (pintype "bidirectional"))
    )
  )
)
